# minime.net
KiCad netlist of a schematic drawn in EAGLE
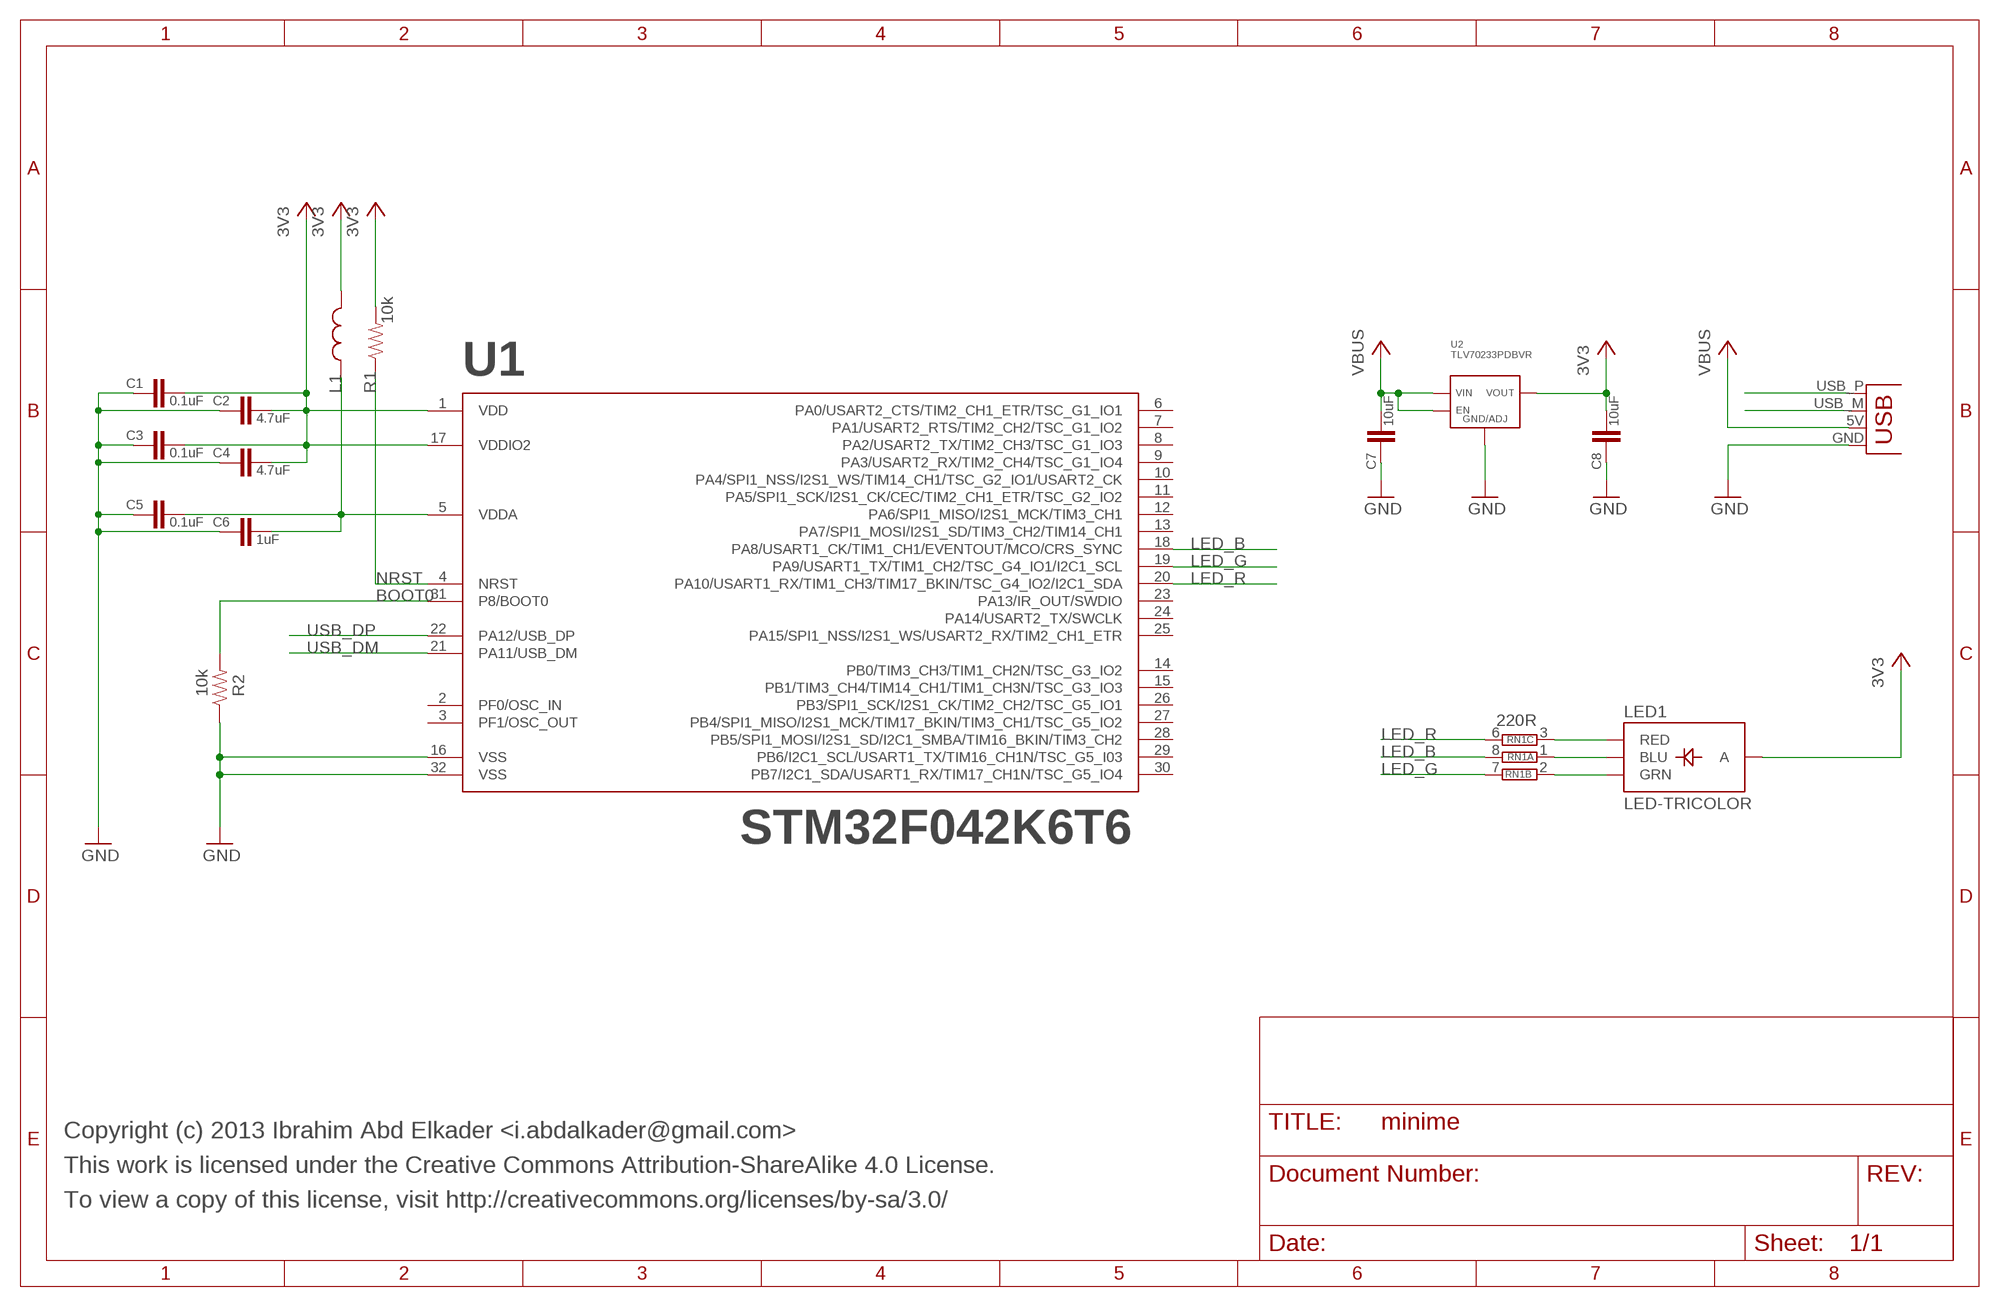
[diagram p0: schematic, sheet 1]

(export (version "E")
  (design (tool "Eeschema 10.0.6"))
  (components
    (comp (ref "C1")
      (value "0.1uF")
      (footprint "eagle-import:0402-CAP")
      (libsource (lib "eagle-import") (part "CAP0402-CAP"))
    )
    (comp (ref "C2")
      (value "4.7uF")
      (footprint "eagle-import:0402-CAP")
      (libsource (lib "eagle-import") (part "CAP0402-CAP"))
    )
    (comp (ref "C3")
      (value "0.1uF")
      (footprint "eagle-import:0402-CAP")
      (libsource (lib "eagle-import") (part "CAP0402-CAP"))
    )
    (comp (ref "C4")
      (value "4.7uF")
      (footprint "eagle-import:0402-CAP")
      (libsource (lib "eagle-import") (part "CAP0402-CAP"))
    )
    (comp (ref "C5")
      (value "0.1uF")
      (footprint "eagle-import:0402-CAP")
      (libsource (lib "eagle-import") (part "CAP0402-CAP"))
    )
    (comp (ref "C6")
      (value "1uF")
      (footprint "eagle-import:0402-CAP")
      (libsource (lib "eagle-import") (part "CAP0402-CAP"))
    )
    (comp (ref "C7")
      (value "10uF")
      (footprint "eagle-import:0805")
      (libsource (lib "eagle-import") (part "CAP0805"))
    )
    (comp (ref "C8")
      (value "10uF")
      (footprint "eagle-import:0805")
      (libsource (lib "eagle-import") (part "CAP0805"))
    )
    (comp (ref "L1")
      (value "MPZ1608S181ATAH0")
      (footprint "eagle-import:0603")
      (libsource (lib "eagle-import") (part "INDUCTOR0603"))
    )
    (comp (ref "LED1")
      (value "LED-TRICOLOR")
      (footprint "eagle-import:LED-TRICOLOR-SMD-MF")
      (libsource (lib "eagle-import") (part "LED-TRICOLOR"))
    )
    (comp (ref "R1")
      (value "10k")
      (footprint "eagle-import:0402-RES")
      (libsource (lib "eagle-import") (part "RESISTOR0402-RES"))
    )
    (comp (ref "R2")
      (value "10k")
      (footprint "eagle-import:0402-RES")
      (libsource (lib "eagle-import") (part "RESISTOR0402-RES"))
    )
    (comp (ref "RN1")
      (value "220R")
      (footprint "eagle-import:EXBV8V")
      (fields (field (name "OC_FARNELL") "unknown") (field (name "OC_NEWARK") "unknown"))
      (libsource (lib "eagle-import") (part "4R-NEXBV8V"))
    )
    (comp (ref "U1")
      (value "STM32F042K6T6")
      (footprint "eagle-import:LQFP32")
      (libsource (lib "eagle-import") (part "STM32F042K6T6"))
    )
    (comp (ref "U2")
      (value "TLV70233PDBVR")
      (footprint "eagle-import:SOT-23-5")
      (libsource (lib "eagle-import") (part "TLV70233PDBVR"))
    )
    (comp (ref "X1")
      (value "SFE_USBPCB")
      (footprint "eagle-import:SFE_USB-A-PCB")
      (libsource (lib "eagle-import") (part "SFE_USBPCB"))
    )
  )
  (nets
    (net (code "1") (name "/BOOT0") (class "Default")
      (node (ref "R2") (pin "2") (pinfunction "2_2") (pintype "passive"))
      (node (ref "U1") (pin "31") (pinfunction "P8/BOOT0_31") (pintype "bidirectional"))
    )
    (net (code "2") (name "/LED_B") (class "Default")
      (node (ref "RN1") (pin "8") (pinfunction "2_8") (pintype "passive"))
      (node (ref "U1") (pin "18") (pinfunction "PA8/USART1_CK/TIM1_CH1/EVENTOUT/MCO/CRS_SYNC_18") (pintype "bidirectional"))
    )
    (net (code "3") (name "/LED_G") (class "Default")
      (node (ref "RN1") (pin "7") (pinfunction "2_7") (pintype "passive"))
      (node (ref "U1") (pin "19") (pinfunction "PA9/USART1_TX/TIM1_CH2/TSC_G4_IO1/I2C1_SCL_19") (pintype "bidirectional"))
    )
    (net (code "4") (name "/LED_R") (class "Default")
      (node (ref "RN1") (pin "6") (pinfunction "2_6") (pintype "passive"))
      (node (ref "U1") (pin "20") (pinfunction "PA10/USART1_RX/TIM1_CH3/TIM17_BKIN/TSC_G4_IO2/I2C1_SDA_20") (pintype "bidirectional"))
    )
    (net (code "5") (name "/NRST") (class "Default")
      (node (ref "R1") (pin "1") (pinfunction "1_1") (pintype "passive"))
      (node (ref "U1") (pin "4") (pinfunction "NRST_4") (pintype "bidirectional"))
    )
    (net (code "6") (name "/USB_DM") (class "Default")
      (node (ref "U1") (pin "21") (pinfunction "PA11/USB_DM_21") (pintype "bidirectional"))
      (node (ref "X1") (pin "USB_M") (pinfunction "D-_USB_M") (pintype "bidirectional"))
    )
    (net (code "7") (name "/USB_DP") (class "Default")
      (node (ref "U1") (pin "22") (pinfunction "PA12/USB_DP_22") (pintype "bidirectional"))
      (node (ref "X1") (pin "USB_P") (pinfunction "D+_USB_P") (pintype "bidirectional"))
    )
    (net (code "8") (name "3V3") (class "Default")
      (node (ref "C1") (pin "1") (pinfunction "1_1") (pintype "passive"))
      (node (ref "C2") (pin "1") (pinfunction "1_1") (pintype "passive"))
      (node (ref "C3") (pin "1") (pinfunction "1_1") (pintype "passive"))
      (node (ref "C4") (pin "1") (pinfunction "1_1") (pintype "passive"))
      (node (ref "C8") (pin "1") (pinfunction "1_1") (pintype "passive"))
      (node (ref "L1") (pin "2") (pinfunction "2_2") (pintype "passive"))
      (node (ref "LED1") (pin "A") (pinfunction "A_A") (pintype "bidirectional"))
      (node (ref "R1") (pin "2") (pinfunction "2_2") (pintype "passive"))
      (node (ref "U1") (pin "1") (pinfunction "VDD_1") (pintype "power_in"))
      (node (ref "U1") (pin "17") (pinfunction "VDDIO2_17") (pintype "power_in"))
      (node (ref "U2") (pin "P$5") (pinfunction "VOUT_P$5") (pintype "bidirectional"))
    )
    (net (code "9") (name "GND") (class "Default")
      (node (ref "C1") (pin "2") (pinfunction "2_2") (pintype "passive"))
      (node (ref "C2") (pin "2") (pinfunction "2_2") (pintype "passive"))
      (node (ref "C3") (pin "2") (pinfunction "2_2") (pintype "passive"))
      (node (ref "C4") (pin "2") (pinfunction "2_2") (pintype "passive"))
      (node (ref "C5") (pin "2") (pinfunction "2_2") (pintype "passive"))
      (node (ref "C6") (pin "2") (pinfunction "2_2") (pintype "passive"))
      (node (ref "C7") (pin "2") (pinfunction "2_2") (pintype "passive"))
      (node (ref "C8") (pin "2") (pinfunction "2_2") (pintype "passive"))
      (node (ref "R2") (pin "1") (pinfunction "1_1") (pintype "passive"))
      (node (ref "U1") (pin "16") (pinfunction "VSS_16") (pintype "power_in"))
      (node (ref "U1") (pin "32") (pinfunction "VSS_32") (pintype "power_in"))
      (node (ref "U2") (pin "P$2") (pinfunction "GND/ADJ_P$2") (pintype "bidirectional"))
      (node (ref "X1") (pin "GND") (pinfunction "GND_GND") (pintype "bidirectional"))
    )
    (net (code "10") (name "Net-(LED1-BLU)") (class "Default")
      (node (ref "LED1") (pin "B") (pinfunction "BLU_B") (pintype "bidirectional"))
      (node (ref "RN1") (pin "1") (pinfunction "1_1") (pintype "passive"))
    )
    (net (code "11") (name "Net-(LED1-GRN)") (class "Default")
      (node (ref "LED1") (pin "G") (pinfunction "GRN_G") (pintype "bidirectional"))
      (node (ref "RN1") (pin "2") (pinfunction "1_2") (pintype "passive"))
    )
    (net (code "12") (name "Net-(LED1-RED)") (class "Default")
      (node (ref "LED1") (pin "R") (pinfunction "RED_R") (pintype "bidirectional"))
      (node (ref "RN1") (pin "3") (pinfunction "1_3") (pintype "passive"))
    )
    (net (code "13") (name "Net-(U1-VDDA)") (class "Default")
      (node (ref "C5") (pin "1") (pinfunction "1_1") (pintype "passive"))
      (node (ref "C6") (pin "1") (pinfunction "1_1") (pintype "passive"))
      (node (ref "L1") (pin "1") (pinfunction "1_1") (pintype "passive"))
      (node (ref "U1") (pin "5") (pinfunction "VDDA_5") (pintype "power_in"))
    )
    (net (code "14") (name "VBUS") (class "Default")
      (node (ref "C7") (pin "1") (pinfunction "1_1") (pintype "passive"))
      (node (ref "U2") (pin "P$1") (pinfunction "VIN_P$1") (pintype "bidirectional"))
      (node (ref "U2") (pin "P$3") (pinfunction "EN_P$3") (pintype "bidirectional"))
      (node (ref "X1") (pin "5V") (pinfunction "VBUS_5V") (pintype "bidirectional"))
    )
    (net (code "15") (name "unconnected-(U1-PA0{slash}USART2_CTS{slash}TIM2_CH1_ETR{slash}TSC_G1_IO1-Pad6)") (class "Default")
      (node (ref "U1") (pin "6") (pinfunction "PA0/USART2_CTS/TIM2_CH1_ETR/TSC_G1_IO1_6") (pintype "bidirectional"))
    )
    (net (code "16") (name "unconnected-(U1-PA1{slash}USART2_RTS{slash}TIM2_CH2{slash}TSC_G1_IO2-Pad7)") (class "Default")
      (node (ref "U1") (pin "7") (pinfunction "PA1/USART2_RTS/TIM2_CH2/TSC_G1_IO2_7") (pintype "bidirectional"))
    )
    (net (code "17") (name "unconnected-(U1-PA2{slash}USART2_TX{slash}TIM2_CH3{slash}TSC_G1_IO3-Pad8)") (class "Default")
      (node (ref "U1") (pin "8") (pinfunction "PA2/USART2_TX/TIM2_CH3/TSC_G1_IO3_8") (pintype "bidirectional"))
    )
    (net (code "18") (name "unconnected-(U1-PA3{slash}USART2_RX{slash}TIM2_CH4{slash}TSC_G1_IO4-Pad9)") (class "Default")
      (node (ref "U1") (pin "9") (pinfunction "PA3/USART2_RX/TIM2_CH4/TSC_G1_IO4_9") (pintype "bidirectional"))
    )
    (net (code "19") (name "unconnected-(U1-PA4{slash}SPI1_NSS{slash}I2S1_WS{slash}TIM14_CH1{slash}TSC_G2_IO1{slash}USART2_CK-Pad10)") (class "Default")
      (node (ref "U1") (pin "10") (pinfunction "PA4/SPI1_NSS/I2S1_WS/TIM14_CH1/TSC_G2_IO1/USART2_CK_10") (pintype "bidirectional"))
    )
    (net (code "20") (name "unconnected-(U1-PA5{slash}SPI1_SCK{slash}I2S1_CK{slash}CEC{slash}TIM2_CH1_ETR{slash}TSC_G2_IO2-Pad11)") (class "Default")
      (node (ref "U1") (pin "11") (pinfunction "PA5/SPI1_SCK/I2S1_CK/CEC/TIM2_CH1_ETR/TSC_G2_IO2_11") (pintype "bidirectional"))
    )
    (net (code "21") (name "unconnected-(U1-PA6{slash}SPI1_MISO{slash}I2S1_MCK{slash}TIM3_CH1-Pad12)") (class "Default")
      (node (ref "U1") (pin "12") (pinfunction "PA6/SPI1_MISO/I2S1_MCK/TIM3_CH1_12") (pintype "bidirectional"))
    )
    (net (code "22") (name "unconnected-(U1-PA7{slash}SPI1_MOSI{slash}I2S1_SD{slash}TIM3_CH2{slash}TIM14_CH1-Pad13)") (class "Default")
      (node (ref "U1") (pin "13") (pinfunction "PA7/SPI1_MOSI/I2S1_SD/TIM3_CH2/TIM14_CH1_13") (pintype "bidirectional"))
    )
    (net (code "23") (name "unconnected-(U1-PA13{slash}IR_OUT{slash}SWDIO-Pad23)") (class "Default")
      (node (ref "U1") (pin "23") (pinfunction "PA13/IR_OUT/SWDIO_23") (pintype "bidirectional"))
    )
    (net (code "24") (name "unconnected-(U1-PA14{slash}USART2_TX{slash}SWCLK-Pad24)") (class "Default")
      (node (ref "U1") (pin "24") (pinfunction "PA14/USART2_TX/SWCLK_24") (pintype "bidirectional"))
    )
    (net (code "25") (name "unconnected-(U1-PA15{slash}SPI1_NSS{slash}I2S1_WS{slash}USART2_RX{slash}TIM2_CH1_ETR-Pad25)") (class "Default")
      (node (ref "U1") (pin "25") (pinfunction "PA15/SPI1_NSS/I2S1_WS/USART2_RX/TIM2_CH1_ETR_25") (pintype "bidirectional"))
    )
    (net (code "26") (name "unconnected-(U1-PB0{slash}TIM3_CH3{slash}TIM1_CH2N{slash}TSC_G3_IO2-Pad14)") (class "Default")
      (node (ref "U1") (pin "14") (pinfunction "PB0/TIM3_CH3/TIM1_CH2N/TSC_G3_IO2_14") (pintype "bidirectional"))
    )
    (net (code "27") (name "unconnected-(U1-PB1{slash}TIM3_CH4{slash}TIM14_CH1{slash}TIM1_CH3N{slash}TSC_G3_IO3-Pad15)") (class "Default")
      (node (ref "U1") (pin "15") (pinfunction "PB1/TIM3_CH4/TIM14_CH1/TIM1_CH3N/TSC_G3_IO3_15") (pintype "bidirectional"))
    )
    (net (code "28") (name "unconnected-(U1-PB3{slash}SPI1_SCK{slash}I2S1_CK{slash}TIM2_CH2{slash}TSC_G5_IO1-Pad26)") (class "Default")
      (node (ref "U1") (pin "26") (pinfunction "PB3/SPI1_SCK/I2S1_CK/TIM2_CH2/TSC_G5_IO1_26") (pintype "bidirectional"))
    )
    (net (code "29") (name "unconnected-(U1-PB4{slash}SPI1_MISO{slash}I2S1_MCK{slash}TIM17_BKIN{slash}TIM3_CH1{slash}TSC_G5_IO2-Pad27)") (class "Default")
      (node (ref "U1") (pin "27") (pinfunction "PB4/SPI1_MISO/I2S1_MCK/TIM17_BKIN/TIM3_CH1/TSC_G5_IO2_27") (pintype "bidirectional"))
    )
    (net (code "30") (name "unconnected-(U1-PB5{slash}SPI1_MOSI{slash}I2S1_SD{slash}I2C1_SMBA{slash}TIM16_BKIN{slash}TIM3_CH2-Pad28)") (class "Default")
      (node (ref "U1") (pin "28") (pinfunction "PB5/SPI1_MOSI/I2S1_SD/I2C1_SMBA/TIM16_BKIN/TIM3_CH2_28") (pintype "bidirectional"))
    )
    (net (code "31") (name "unconnected-(U1-PB6{slash}I2C1_SCL{slash}USART1_TX{slash}TIM16_CH1N{slash}TSC_G5_I03-Pad29)") (class "Default")
      (node (ref "U1") (pin "29") (pinfunction "PB6/I2C1_SCL/USART1_TX/TIM16_CH1N/TSC_G5_I03_29") (pintype "bidirectional"))
    )
    (net (code "32") (name "unconnected-(U1-PB7{slash}I2C1_SDA{slash}USART1_RX{slash}TIM17_CH1N{slash}TSC_G5_IO4-Pad30)") (class "Default")
      (node (ref "U1") (pin "30") (pinfunction "PB7/I2C1_SDA/USART1_RX/TIM17_CH1N/TSC_G5_IO4_30") (pintype "bidirectional"))
    )
    (net (code "33") (name "unconnected-(U1-PF0{slash}OSC_IN-Pad2)") (class "Default")
      (node (ref "U1") (pin "2") (pinfunction "PF0/OSC_IN_2") (pintype "bidirectional"))
    )
    (net (code "34") (name "unconnected-(U1-PF1{slash}OSC_OUT-Pad3)") (class "Default")
      (node (ref "U1") (pin "3") (pinfunction "PF1/OSC_OUT_3") (pintype "bidirectional"))
    )
  )
)
